# Sheet1.net
KiCad netlist of a schematic drawn in Altium Designer
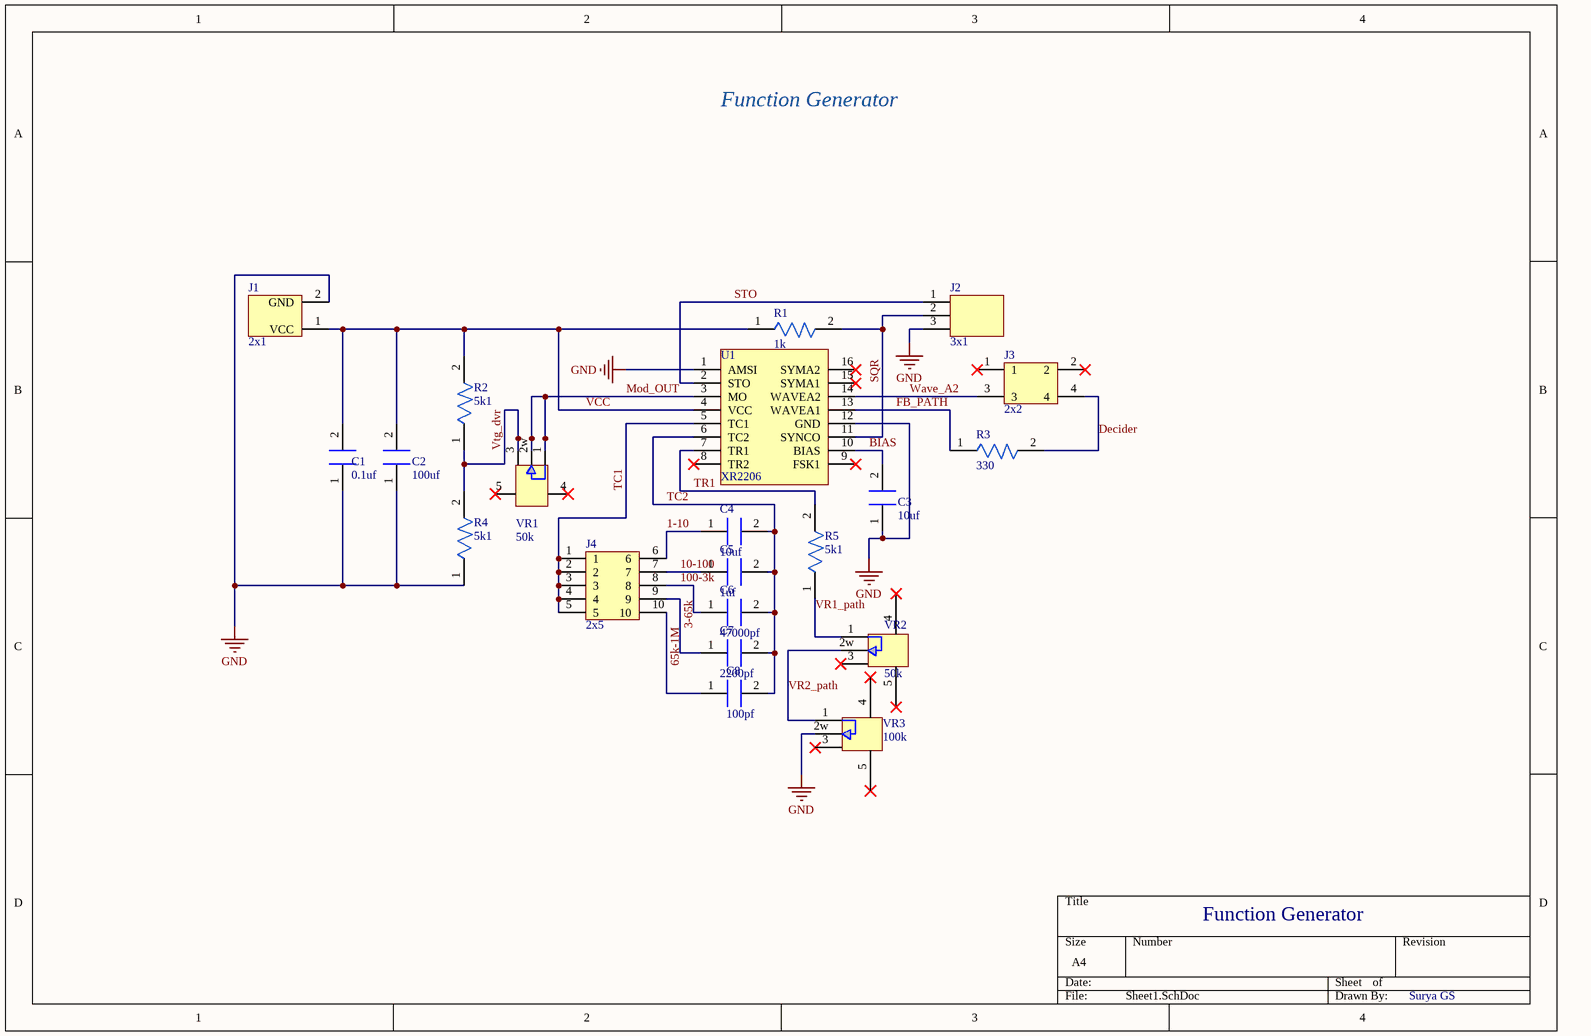
[diagram p0: Sheet1.SchDoc]

(export (version "E")
  (design (tool "Eeschema 10.0.6"))
  (components
    (comp (ref "C1")
      (value "0.1uf")
      (footprint "PCBComponent_1")
      (fields
        (field (name "MANUFACTURER") "United Chemi-Con")
        (field (name "MANUFACTURER PART NUMBER") "KTD101B107M99A0B00")
        (field (name "TOLERANCE") "20%")
      )
      (libsource (lib "Schlib1") (part "Capacitor_3"))
    )
    (comp (ref "C2")
      (value "100uf")
      (footprint "PCBComponent_1")
      (fields
        (field (name "MANUFACTURER") "United Chemi-Con")
        (field (name "MANUFACTURER PART NUMBER") "KTD101B107M99A0B00")
        (field (name "TOLERANCE") "20%")
      )
      (libsource (lib "Schlib1") (part "Capacitor"))
    )
    (comp (ref "C3")
      (value "10uf")
      (footprint "PCBComponent_1")
      (fields
        (field (name "MANUFACTURER") "United Chemi-Con")
        (field (name "MANUFACTURER PART NUMBER") "KTD101B107M99A0B00")
        (field (name "TOLERANCE") "20%")
      )
      (libsource (lib "Schlib1") (part "Capacitor_4"))
    )
    (comp (ref "C4")
      (value "10uf")
      (footprint "PCBComponent_1")
      (fields
        (field (name "MANUFACTURER") "United Chemi-Con")
        (field (name "MANUFACTURER PART NUMBER") "KTD101B107M99A0B00")
        (field (name "TOLERANCE") "20%")
      )
      (libsource (lib "Schlib1") (part "Capacitor_5"))
    )
    (comp (ref "C5")
      (value "1uf")
      (footprint "PCBComponent_1")
      (fields
        (field (name "MANUFACTURER") "United Chemi-Con")
        (field (name "MANUFACTURER PART NUMBER") "KTD101B107M99A0B00")
        (field (name "TOLERANCE") "20%")
      )
      (libsource (lib "Schlib1") (part "Capacitor_1"))
    )
    (comp (ref "C6")
      (value "47000pf")
      (footprint "PCBComponent_1")
      (fields
        (field (name "MANUFACTURER") "United Chemi-Con")
        (field (name "MANUFACTURER PART NUMBER") "KTD101B107M99A0B00")
        (field (name "TOLERANCE") "20%")
      )
      (libsource (lib "Schlib1") (part "Capacitor_2"))
    )
    (comp (ref "C7")
      (value "2200pf")
      (footprint "PCBComponent_1")
      (fields
        (field (name "MANUFACTURER") "United Chemi-Con")
        (field (name "MANUFACTURER PART NUMBER") "KTD101B107M99A0B00")
        (field (name "TOLERANCE") "20%")
      )
      (libsource (lib "Schlib1") (part "Capacitor_6"))
    )
    (comp (ref "C8")
      (value "100pf")
      (footprint "PCBComponent_1")
      (fields
        (field (name "MANUFACTURER") "United Chemi-Con")
        (field (name "MANUFACTURER PART NUMBER") "KTD101B107M99A0B00")
        (field (name "TOLERANCE") "20%")
      )
      (libsource (lib "Schlib1") (part "Capacitor_7"))
    )
    (comp (ref "J1")
      (value "2x1")
      (footprint "PCBComponent_1 - duplicate4")
      (fields
        (field (name "MANUFACTURER") "Sullins")
        (field (name "MANUFACTURER PART NUMBER") "PPPC022LFBN-RC")
      )
      (libsource (lib "Schlib1") (part "Header_2"))
    )
    (comp (ref "J2")
      (value "3x1")
      (footprint "PCBComponent_1 - duplicate7")
      (fields
        (field (name "MANUFACTURER") "Sullins")
        (field (name "MANUFACTURER PART NUMBER") "PPPC022LFBN-RC")
      )
      (libsource (lib "Schlib1") (part "Header_3"))
    )
    (comp (ref "J3")
      (value "2x2")
      (footprint "PCBComponent_1 - duplicate6")
      (fields
        (field (name "MANUFACTURER") "Sullins")
        (field (name "MANUFACTURER PART NUMBER") "PPPC022LFBN-RC")
      )
      (libsource (lib "Schlib1") (part "Header"))
    )
    (comp (ref "J4")
      (value "2x5")
      (footprint "PCBComponent_1 - duplicate5")
      (fields
        (field (name "MANUFACTURER") "Sullins")
        (field (name "MANUFACTURER PART NUMBER") "PPPC022LFBN-RC")
      )
      (libsource (lib "Schlib1") (part "Header_1"))
    )
    (comp (ref "R1")
      (value "1k")
      (footprint "PCBComponent_1 - duplicate")
      (fields
        (field (name "MANUFACTURER") "Yageo")
        (field (name "MANUFACTURER PART NUMBER") "RC0402FR-07267KL")
        (field (name "TOLERANCE") "1%")
      )
      (libsource (lib "Schlib1") (part "Resistor"))
    )
    (comp (ref "R2")
      (value "5k1")
      (footprint "PCBComponent_1 - duplicate")
      (fields
        (field (name "MANUFACTURER") "Yageo Group")
        (field (name "MANUFACTURER PART NUMBER") "RC0603FR-075K1L")
        (field (name "TOLERANCE") "1%")
      )
      (libsource (lib "Schlib1") (part "Resistor_2"))
    )
    (comp (ref "R3")
      (value "330")
      (footprint "PCBComponent_1 - duplicate")
      (fields
        (field (name "MANUFACTURER") "TE Connectivity")
        (field (name "MANUFACTURER PART NUMBER") "CRGP2512F330R")
        (field (name "TOLERANCE") "1%")
      )
      (libsource (lib "Schlib1") (part "Resistor_1"))
    )
    (comp (ref "R4")
      (value "5k1")
      (footprint "PCBComponent_1 - duplicate")
      (fields
        (field (name "MANUFACTURER") "Yageo Group")
        (field (name "MANUFACTURER PART NUMBER") "RC0603FR-075K1L")
        (field (name "TOLERANCE") "1%")
      )
      (libsource (lib "Schlib1") (part "Resistor_2"))
    )
    (comp (ref "R5")
      (value "5k1")
      (footprint "PCBComponent_1 - duplicate")
      (fields
        (field (name "MANUFACTURER") "Yageo Group")
        (field (name "MANUFACTURER PART NUMBER") "RC0603FR-075K1L")
        (field (name "TOLERANCE") "1%")
      )
      (libsource (lib "Schlib1") (part "Resistor_2"))
    )
    (comp (ref "U1")
      (value "XR2206")
      (footprint "PCBComponent_1 - duplicate2")
      (libsource (lib "Schlib1") (part "XR2206CP-F"))
    )
    (comp (ref "VR1")
      (value "50k")
      (footprint "PCBComponent_1 - duplicate3")
      (fields
        (field (name "MANUFACTURER") "Bourns")
        (field (name "MANUFACTURER PART NUMBER") "PV36W503C01B00")
        (field (name "TOLERANCE") "10%")
      )
      (libsource (lib "Schlib1") (part "Potentiometer"))
    )
    (comp (ref "VR2")
      (value "50k")
      (footprint "PCBComponent_1 - duplicate3")
      (fields
        (field (name "MANUFACTURER") "Bourns")
        (field (name "MANUFACTURER PART NUMBER") "PV36W503C01B00")
        (field (name "TOLERANCE") "10%")
      )
      (libsource (lib "Schlib1") (part "Potentiometer_1"))
    )
    (comp (ref "VR3")
      (value "100k")
      (footprint "PCBComponent_1 - duplicate3")
      (fields
        (field (name "MANUFACTURER") "Bourns")
        (field (name "MANUFACTURER PART NUMBER") "PV36W503C01B00")
        (field (name "TOLERANCE") "10%")
      )
      (libsource (lib "Schlib1") (part "Potentiometer_2"))
    )
  )
  (nets
    (net (code "1") (name "/1-10") (class "Default")
      (node (ref "C4") (pin "1") (pinfunction "1_1") (pintype "passive"))
      (node (ref "J4") (pin "6") (pinfunction "6_6") (pintype "passive"))
    )
    (net (code "2") (name "/3-65k") (class "Default")
      (node (ref "C7") (pin "1") (pinfunction "1_1") (pintype "passive"))
      (node (ref "J4") (pin "9") (pinfunction "9_9") (pintype "passive"))
    )
    (net (code "3") (name "/10-100") (class "Default")
      (node (ref "C5") (pin "1") (pinfunction "1_1") (pintype "passive"))
      (node (ref "J4") (pin "7") (pinfunction "7_7") (pintype "passive"))
    )
    (net (code "4") (name "/65k-1M") (class "Default")
      (node (ref "C8") (pin "1") (pinfunction "1_1") (pintype "passive"))
      (node (ref "J4") (pin "10") (pinfunction "10_10") (pintype "passive"))
    )
    (net (code "5") (name "/100-3k") (class "Default")
      (node (ref "C6") (pin "1") (pinfunction "1_1") (pintype "passive"))
      (node (ref "J4") (pin "8") (pinfunction "8_8") (pintype "passive"))
    )
    (net (code "7") (name "/BIAS") (class "Default")
      (node (ref "C3") (pin "2") (pinfunction "2_2") (pintype "passive"))
      (node (ref "U1") (pin "10") (pinfunction "BIAS_10") (pintype "passive"))
    )
    (net (code "8") (name "/Decider") (class "Default")
      (node (ref "J3") (pin "4") (pinfunction "4_4") (pintype "passive"))
      (node (ref "R3") (pin "2") (pinfunction "2_2") (pintype "passive"))
    )
    (net (code "9") (name "/FB_PATH") (class "Default")
      (node (ref "R3") (pin "1") (pinfunction "1_1") (pintype "passive"))
      (node (ref "U1") (pin "13") (pinfunction "WAVEA1_13") (pintype "passive"))
    )
    (net (code "10") (name "/Mod_OUT") (class "Default")
      (node (ref "U1") (pin "3") (pinfunction "MO_3") (pintype "passive"))
      (node (ref "VR1") (pin "1") (pinfunction "1_1") (pintype "passive"))
      (node (ref "VR1") (pin "2w") (pinfunction "WPR_2w") (pintype "passive"))
    )
    (net (code "11") (name "/SQR") (class "Default")
      (node (ref "J2") (pin "2") (pinfunction "SQU_2") (pintype "passive"))
      (node (ref "R1") (pin "2") (pinfunction "2_2") (pintype "passive"))
      (node (ref "U1") (pin "11") (pinfunction "SYNCO_11") (pintype "passive"))
    )
    (net (code "12") (name "/STO") (class "Default")
      (node (ref "J2") (pin "1") (pinfunction "SIN/TRI_1") (pintype "passive"))
      (node (ref "U1") (pin "2") (pinfunction "STO_2") (pintype "passive"))
    )
    (net (code "13") (name "/TC1") (class "Default")
      (node (ref "J4") (pin "1") (pinfunction "1_1") (pintype "passive"))
      (node (ref "J4") (pin "2") (pinfunction "2_2") (pintype "passive"))
      (node (ref "J4") (pin "3") (pinfunction "3_3") (pintype "passive"))
      (node (ref "J4") (pin "4") (pinfunction "4_4") (pintype "passive"))
      (node (ref "J4") (pin "5") (pinfunction "5_5") (pintype "passive"))
      (node (ref "U1") (pin "5") (pinfunction "TC1_5") (pintype "passive"))
    )
    (net (code "14") (name "/TC2") (class "Default")
      (node (ref "C4") (pin "2") (pinfunction "2_2") (pintype "passive"))
      (node (ref "C5") (pin "2") (pinfunction "2_2") (pintype "passive"))
      (node (ref "C6") (pin "2") (pinfunction "2_2") (pintype "passive"))
      (node (ref "C7") (pin "2") (pinfunction "2_2") (pintype "passive"))
      (node (ref "C8") (pin "2") (pinfunction "2_2") (pintype "passive"))
      (node (ref "U1") (pin "6") (pinfunction "TC2_6") (pintype "passive"))
    )
    (net (code "15") (name "/TR1") (class "Default")
      (node (ref "R5") (pin "2") (pinfunction "2_2") (pintype "passive"))
      (node (ref "U1") (pin "7") (pinfunction "TR1_7") (pintype "passive"))
    )
    (net (code "16") (name "/VCC") (class "Default")
      (node (ref "C1") (pin "2") (pinfunction "2_2") (pintype "passive"))
      (node (ref "C2") (pin "2") (pinfunction "2_2") (pintype "passive"))
      (node (ref "J1") (pin "1") (pinfunction "VCC_1") (pintype "power_in"))
      (node (ref "R1") (pin "1") (pinfunction "1_1") (pintype "passive"))
      (node (ref "R2") (pin "2") (pinfunction "2_2") (pintype "passive"))
      (node (ref "U1") (pin "4") (pinfunction "VCC_4") (pintype "passive"))
    )
    (net (code "17") (name "/VR1_path") (class "Default")
      (node (ref "R5") (pin "1") (pinfunction "1_1") (pintype "passive"))
      (node (ref "VR2") (pin "1") (pinfunction "1_1") (pintype "passive"))
    )
    (net (code "18") (name "/VR2_path") (class "Default")
      (node (ref "VR2") (pin "2w") (pinfunction "WPR_2w") (pintype "passive"))
      (node (ref "VR3") (pin "1") (pinfunction "1_1") (pintype "passive"))
    )
    (net (code "19") (name "/Vtg_dvr") (class "Default")
      (node (ref "R2") (pin "1") (pinfunction "1_1") (pintype "passive"))
      (node (ref "R4") (pin "2") (pinfunction "2_2") (pintype "passive"))
      (node (ref "VR1") (pin "3") (pinfunction "12_3") (pintype "passive"))
    )
    (net (code "20") (name "/Wave_A2") (class "Default")
      (node (ref "J3") (pin "3") (pinfunction "3_3") (pintype "passive"))
      (node (ref "U1") (pin "14") (pinfunction "WAVEA2_14") (pintype "passive"))
    )
    (net (code "21") (name "GND") (class "Default")
      (node (ref "C1") (pin "1") (pinfunction "1_1") (pintype "passive"))
      (node (ref "C2") (pin "1") (pinfunction "1_1") (pintype "passive"))
      (node (ref "C3") (pin "1") (pinfunction "1_1") (pintype "passive"))
      (node (ref "J1") (pin "2") (pinfunction "GND_2") (pintype "power_in"))
      (node (ref "J2") (pin "3") (pinfunction "GND_3") (pintype "passive"))
      (node (ref "R4") (pin "1") (pinfunction "1_1") (pintype "passive"))
      (node (ref "U1") (pin "1") (pinfunction "AMSI_1") (pintype "passive"))
      (node (ref "U1") (pin "12") (pinfunction "GND_12") (pintype "passive"))
      (node (ref "VR3") (pin "2w") (pinfunction "WPR_2w") (pintype "passive"))
    )
    (net (code "22") (name "unconnected-(J3-Pad1)") (class "Default")
      (node (ref "J3") (pin "1") (pinfunction "1_1") (pintype "passive+no_connect"))
    )
    (net (code "23") (name "unconnected-(J3-Pad2)") (class "Default")
      (node (ref "J3") (pin "2") (pinfunction "2_2") (pintype "passive+no_connect"))
    )
    (net (code "24") (name "unconnected-(U1-FSK1-Pad9)") (class "Default")
      (node (ref "U1") (pin "9") (pinfunction "FSK1_9") (pintype "passive+no_connect"))
    )
    (net (code "25") (name "unconnected-(U1-SYMA1-Pad15)") (class "Default")
      (node (ref "U1") (pin "15") (pinfunction "SYMA1_15") (pintype "passive+no_connect"))
    )
    (net (code "26") (name "unconnected-(U1-SYMA2-Pad16)") (class "Default")
      (node (ref "U1") (pin "16") (pinfunction "SYMA2_16") (pintype "passive+no_connect"))
    )
    (net (code "27") (name "unconnected-(U1-TR2-Pad8)") (class "Default")
      (node (ref "U1") (pin "8") (pinfunction "TR2_8") (pintype "passive+no_connect"))
    )
    (net (code "28") (name "unconnected-(VR1-WPR-Pad4)") (class "Default")
      (node (ref "VR1") (pin "4") (pinfunction "WPR_4") (pintype "passive+no_connect"))
    )
    (net (code "29") (name "unconnected-(VR1-WPR-Pad5)") (class "Default")
      (node (ref "VR1") (pin "5") (pinfunction "WPR_5") (pintype "passive+no_connect"))
    )
    (net (code "30") (name "unconnected-(VR2-12-Pad3)") (class "Default")
      (node (ref "VR2") (pin "3") (pinfunction "12_3") (pintype "passive+no_connect"))
    )
    (net (code "31") (name "unconnected-(VR2-WPR-Pad4)") (class "Default")
      (node (ref "VR2") (pin "4") (pinfunction "WPR_4") (pintype "passive+no_connect"))
    )
    (net (code "32") (name "unconnected-(VR2-WPR-Pad5)") (class "Default")
      (node (ref "VR2") (pin "5") (pinfunction "WPR_5") (pintype "passive+no_connect"))
    )
    (net (code "33") (name "unconnected-(VR3-12-Pad3)") (class "Default")
      (node (ref "VR3") (pin "3") (pinfunction "12_3") (pintype "passive+no_connect"))
    )
    (net (code "34") (name "unconnected-(VR3-WPR-Pad4)") (class "Default")
      (node (ref "VR3") (pin "4") (pinfunction "WPR_4") (pintype "passive+no_connect"))
    )
    (net (code "35") (name "unconnected-(VR3-WPR-Pad5)") (class "Default")
      (node (ref "VR3") (pin "5") (pinfunction "WPR_5") (pintype "passive+no_connect"))
    )
  )
)
